# IO_Peripherals.net
KiCad netlist of a schematic drawn in Altium Designer
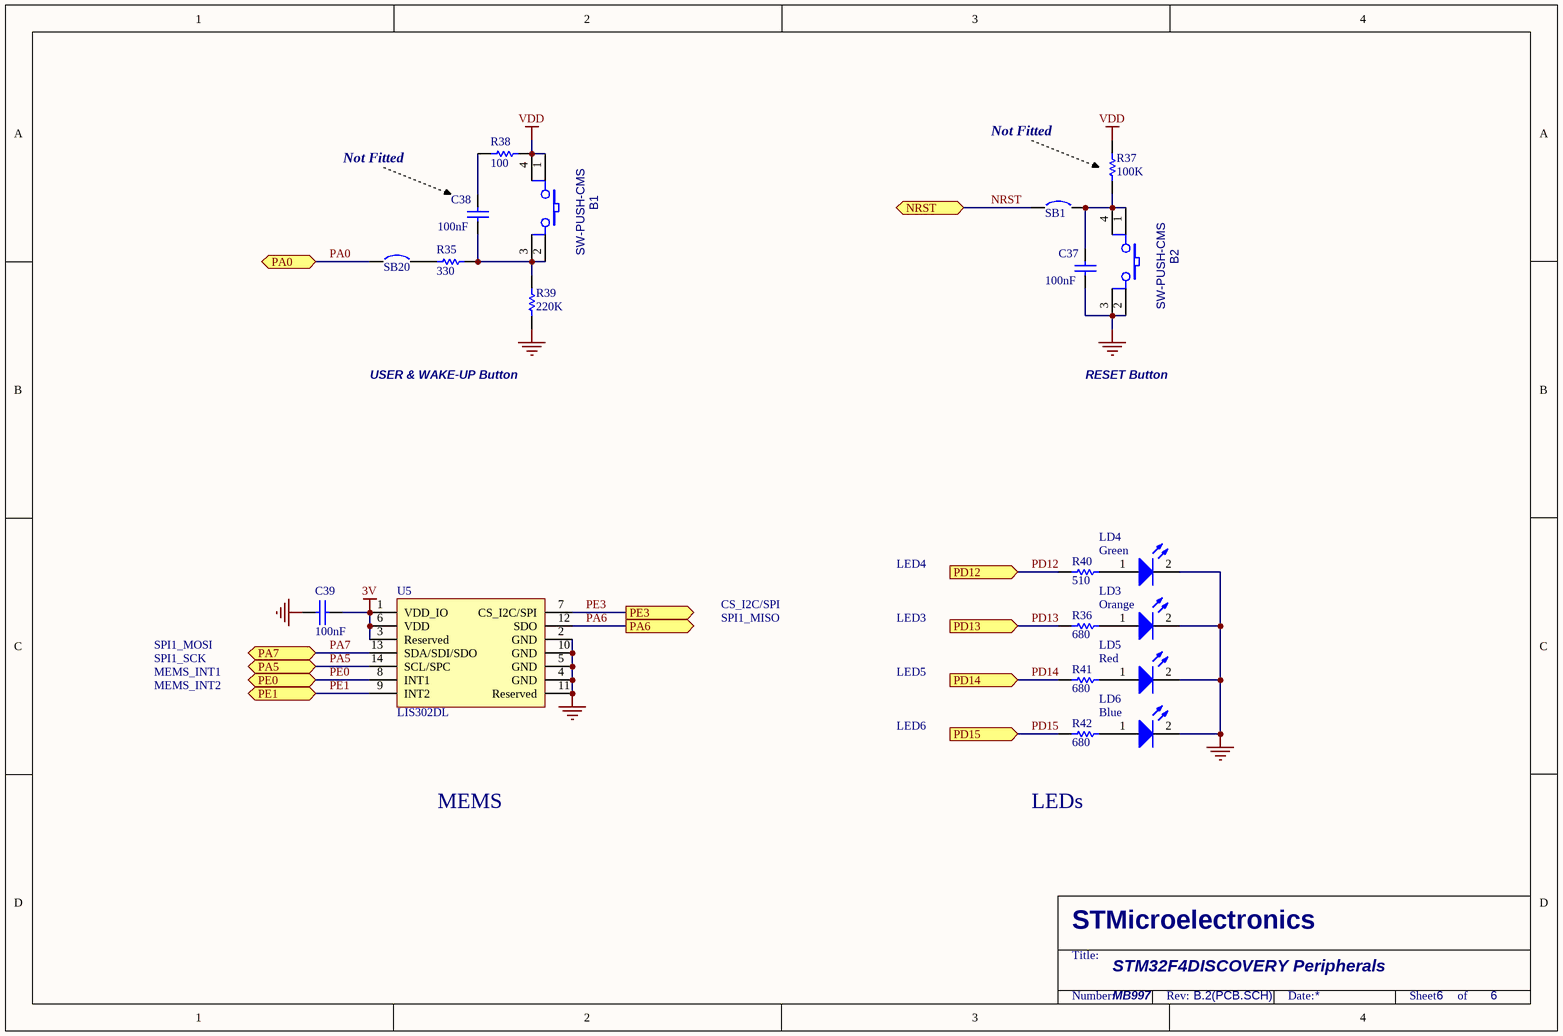
[diagram p0: IO Peripherals.SchDoc]

(export (version "E")
  (design (tool "Eeschema 10.0.6"))
  (components
    (comp (ref "B1")
      (value "SW-PUSH-CMS")
      (footprint "BP1CMS")
      (description "Non-Open Push-Button 0.1A 24V")
      (libsource (lib "MB913_1") (part "SW-PUSH-CMS"))
    )
    (comp (ref "B2")
      (value "SW-PUSH-CMS")
      (footprint "BP1CMS")
      (description "Non-Open Push-Button 0.1A 24V")
      (libsource (lib "MB913_1") (part "SW-PUSH-CMS"))
    )
    (comp (ref "C37")
      (value "100nF")
      (footprint "0603C")
      (description "Capacitor")
      (fields (field (name "PUBLISHER") "Altium Limited"))
      (libsource (lib "Miscellaneous Devices") (part "CAP"))
    )
    (comp (ref "C38")
      (value "100nF")
      (footprint "0603C")
      (description "Capacitor")
      (fields (field (name "PUBLISHER") "Altium Limited"))
      (libsource (lib "Miscellaneous Devices") (part "CAP"))
    )
    (comp (ref "C39")
      (value "100nF")
      (footprint "0402C")
      (description "Capacitor")
      (libsource (lib "*") (part "CAP"))
    )
    (comp (ref "LD3")
      (value "Orange")
      (footprint "0603D")
      (description "Typical RED, GREEN, YELLOW, AMBER GaAs LED")
      (fields (field (name "PUBLISHER") "Altium Limited"))
      (libsource (lib "Miscellaneous Devices") (part "LED2"))
    )
    (comp (ref "LD4")
      (value "Green")
      (footprint "0603D")
      (description "Typical RED, GREEN, YELLOW, AMBER GaAs LED")
      (fields (field (name "PUBLISHER") "Altium Limited"))
      (libsource (lib "Miscellaneous Devices") (part "LED2"))
    )
    (comp (ref "LD5")
      (value "Red")
      (footprint "0603D")
      (description "Typical RED, GREEN, YELLOW, AMBER GaAs LED")
      (fields (field (name "PUBLISHER") "Altium Limited"))
      (libsource (lib "Miscellaneous Devices") (part "LED2"))
    )
    (comp (ref "LD6")
      (value "Blue")
      (footprint "0603D")
      (description "Typical RED, GREEN, YELLOW, AMBER GaAs LED")
      (fields (field (name "PUBLISHER") "Altium Limited"))
      (libsource (lib "Miscellaneous Devices") (part "LED2"))
    )
    (comp (ref "R35")
      (value "330")
      (footprint "0402R")
      (description "Resistor")
      (fields (field (name "PUBLISHER") "Altium Limited"))
      (libsource (lib "Miscellaneous Devices") (part "res1"))
    )
    (comp (ref "R36")
      (value "680")
      (footprint "0603R")
      (description "Resistor")
      (fields (field (name "PUBLISHER") "Altium Limited"))
      (libsource (lib "Miscellaneous Devices") (part "Res1"))
    )
    (comp (ref "R37")
      (value "100K")
      (footprint "0402R")
      (description "Resistor")
      (fields (field (name "PUBLISHER") "Altium Limited"))
      (libsource (lib "Miscellaneous Devices") (part "res1"))
    )
    (comp (ref "R38")
      (value "100")
      (footprint "0402R")
      (description "Resistor")
      (fields (field (name "PUBLISHER") "Altium Limited"))
      (libsource (lib "Miscellaneous Devices") (part "res1"))
    )
    (comp (ref "R39")
      (value "220K")
      (description "Resistor")
      (fields (field (name "PUBLISHER") "Altium Limited"))
      (libsource (lib "Miscellaneous Devices") (part "res1"))
    )
    (comp (ref "R40")
      (value "510")
      (footprint "0603R")
      (description "Resistor")
      (fields (field (name "PUBLISHER") "Altium Limited"))
      (libsource (lib "Miscellaneous Devices") (part "Res1"))
    )
    (comp (ref "R41")
      (value "680")
      (footprint "0603R")
      (description "Resistor")
      (fields (field (name "PUBLISHER") "Altium Limited"))
      (libsource (lib "Miscellaneous Devices") (part "Res1"))
    )
    (comp (ref "R42")
      (value "680")
      (footprint "0603R")
      (description "Resistor")
      (fields (field (name "PUBLISHER") "Altium Limited"))
      (libsource (lib "Miscellaneous Devices") (part "Res1"))
    )
    (comp (ref "SB1")
      (value "Circuit Breaker")
      (footprint "JP2_SMD")
      (fields (field (name "PUBLISHER") "Altium Limited"))
      (libsource (lib "MB915") (part "Circuit Breaker"))
    )
    (comp (ref "SB20")
      (value "Circuit Breaker")
      (footprint "JP2_SMD")
      (fields (field (name "PUBLISHER") "Altium Limited"))
      (libsource (lib "MB915") (part "Circuit Breaker"))
    )
    (comp (ref "U5")
      (value "LIS302DL")
      (footprint "LGA14(3*5)")
      (description "MEMS motion sensor 3-axis - ±2g/±8g smart digital output \"piccolo\" accelerometer")
      (libsource (lib "MB997") (part "LIS302DL"))
    )
  )
  (nets
    (net (code "1") (name "/NRST") (class "Default")
      (node (ref "SB1") (pin "1") (pinfunction "1_1") (pintype "passive"))
    )
    (net (code "2") (name "/PA0") (class "Default")
      (node (ref "SB20") (pin "1") (pinfunction "1_1") (pintype "passive"))
    )
    (net (code "3") (name "/PA5") (class "Default")
      (node (ref "U5") (pin "14") (pinfunction "SCL/SPC_14") (pintype "passive"))
    )
    (net (code "4") (name "/PA6") (class "Default")
      (node (ref "U5") (pin "12") (pinfunction "SDO_12") (pintype "passive"))
    )
    (net (code "5") (name "/PA7") (class "Default")
      (node (ref "U5") (pin "13") (pinfunction "SDA/SDI/SDO_13") (pintype "passive"))
    )
    (net (code "6") (name "/PD12") (class "Default")
      (node (ref "R40") (pin "2") (pinfunction "2_2") (pintype "passive"))
    )
    (net (code "7") (name "/PD13") (class "Default")
      (node (ref "R36") (pin "2") (pinfunction "2_2") (pintype "passive"))
    )
    (net (code "8") (name "/PD14") (class "Default")
      (node (ref "R41") (pin "2") (pinfunction "2_2") (pintype "passive"))
    )
    (net (code "9") (name "/PD15") (class "Default")
      (node (ref "R42") (pin "2") (pinfunction "2_2") (pintype "passive"))
    )
    (net (code "10") (name "/PE0") (class "Default")
      (node (ref "U5") (pin "8") (pinfunction "INT1_8") (pintype "passive"))
    )
    (net (code "11") (name "/PE1") (class "Default")
      (node (ref "U5") (pin "9") (pinfunction "INT2_9") (pintype "passive"))
    )
    (net (code "12") (name "/PE3") (class "Default")
      (node (ref "U5") (pin "7") (pinfunction "CS_I2C/SPI_7") (pintype "passive"))
    )
    (net (code "13") (name "3V") (class "Default")
      (node (ref "C39") (pin "2") (pinfunction "2_2") (pintype "passive"))
      (node (ref "U5") (pin "1") (pinfunction "VDD_IO_1") (pintype "passive"))
      (node (ref "U5") (pin "3") (pinfunction "Reserved_3") (pintype "passive"))
      (node (ref "U5") (pin "6") (pinfunction "VDD_6") (pintype "passive"))
    )
    (net (code "14") (name "GND") (class "Default")
      (node (ref "B2") (pin "2") (pinfunction "2_2") (pintype "passive"))
      (node (ref "B2") (pin "3") (pinfunction "3_3") (pintype "passive"))
      (node (ref "C37") (pin "1") (pinfunction "1_1") (pintype "passive"))
      (node (ref "C39") (pin "1") (pinfunction "1_1") (pintype "passive"))
      (node (ref "LD3") (pin "2") (pinfunction "K_2") (pintype "passive"))
      (node (ref "LD4") (pin "2") (pinfunction "K_2") (pintype "passive"))
      (node (ref "LD5") (pin "2") (pinfunction "K_2") (pintype "passive"))
      (node (ref "LD6") (pin "2") (pinfunction "K_2") (pintype "passive"))
      (node (ref "R39") (pin "1") (pinfunction "1_1") (pintype "passive"))
      (node (ref "U5") (pin "10") (pinfunction "GND_10") (pintype "passive"))
      (node (ref "U5") (pin "11") (pinfunction "Reserved_11") (pintype "passive"))
      (node (ref "U5") (pin "2") (pinfunction "GND_2") (pintype "passive"))
      (node (ref "U5") (pin "4") (pinfunction "GND_4") (pintype "passive"))
      (node (ref "U5") (pin "5") (pinfunction "GND_5") (pintype "passive"))
    )
    (net (code "15") (name "Net-(B1-Pad2)") (class "Default")
      (node (ref "B1") (pin "2") (pinfunction "2_2") (pintype "passive"))
      (node (ref "B1") (pin "3") (pinfunction "3_3") (pintype "passive"))
      (node (ref "C38") (pin "1") (pinfunction "1_1") (pintype "passive"))
      (node (ref "R35") (pin "2") (pinfunction "2_2") (pintype "passive"))
      (node (ref "R39") (pin "2") (pinfunction "2_2") (pintype "passive"))
    )
    (net (code "16") (name "Net-(B2-Pad1)") (class "Default")
      (node (ref "B2") (pin "1") (pinfunction "1_1") (pintype "passive"))
      (node (ref "B2") (pin "4") (pinfunction "4_4") (pintype "passive"))
      (node (ref "C37") (pin "2") (pinfunction "2_2") (pintype "passive"))
      (node (ref "R37") (pin "1") (pinfunction "1_1") (pintype "passive"))
      (node (ref "SB1") (pin "2") (pinfunction "2_2") (pintype "passive"))
    )
    (net (code "17") (name "Net-(C38-Pad2)") (class "Default")
      (node (ref "C38") (pin "2") (pinfunction "2_2") (pintype "passive"))
      (node (ref "R38") (pin "1") (pinfunction "1_1") (pintype "passive"))
    )
    (net (code "18") (name "Net-(LD3-A)") (class "Default")
      (node (ref "LD3") (pin "1") (pinfunction "A_1") (pintype "passive"))
      (node (ref "R36") (pin "1") (pinfunction "1_1") (pintype "passive"))
    )
    (net (code "19") (name "Net-(LD4-A)") (class "Default")
      (node (ref "LD4") (pin "1") (pinfunction "A_1") (pintype "passive"))
      (node (ref "R40") (pin "1") (pinfunction "1_1") (pintype "passive"))
    )
    (net (code "20") (name "Net-(LD5-A)") (class "Default")
      (node (ref "LD5") (pin "1") (pinfunction "A_1") (pintype "passive"))
      (node (ref "R41") (pin "1") (pinfunction "1_1") (pintype "passive"))
    )
    (net (code "21") (name "Net-(LD6-A)") (class "Default")
      (node (ref "LD6") (pin "1") (pinfunction "A_1") (pintype "passive"))
      (node (ref "R42") (pin "1") (pinfunction "1_1") (pintype "passive"))
    )
    (net (code "22") (name "Net-(R35-Pad1)") (class "Default")
      (node (ref "R35") (pin "1") (pinfunction "1_1") (pintype "passive"))
      (node (ref "SB20") (pin "2") (pinfunction "2_2") (pintype "passive"))
    )
    (net (code "23") (name "VDD") (class "Default")
      (node (ref "B1") (pin "1") (pinfunction "1_1") (pintype "passive"))
      (node (ref "B1") (pin "4") (pinfunction "4_4") (pintype "passive"))
      (node (ref "R37") (pin "2") (pinfunction "2_2") (pintype "passive"))
      (node (ref "R38") (pin "2") (pinfunction "2_2") (pintype "passive"))
    )
  )
)
